# pca10040_sheet5_power_supply.net
KiCad netlist of a schematic drawn in Altium Designer
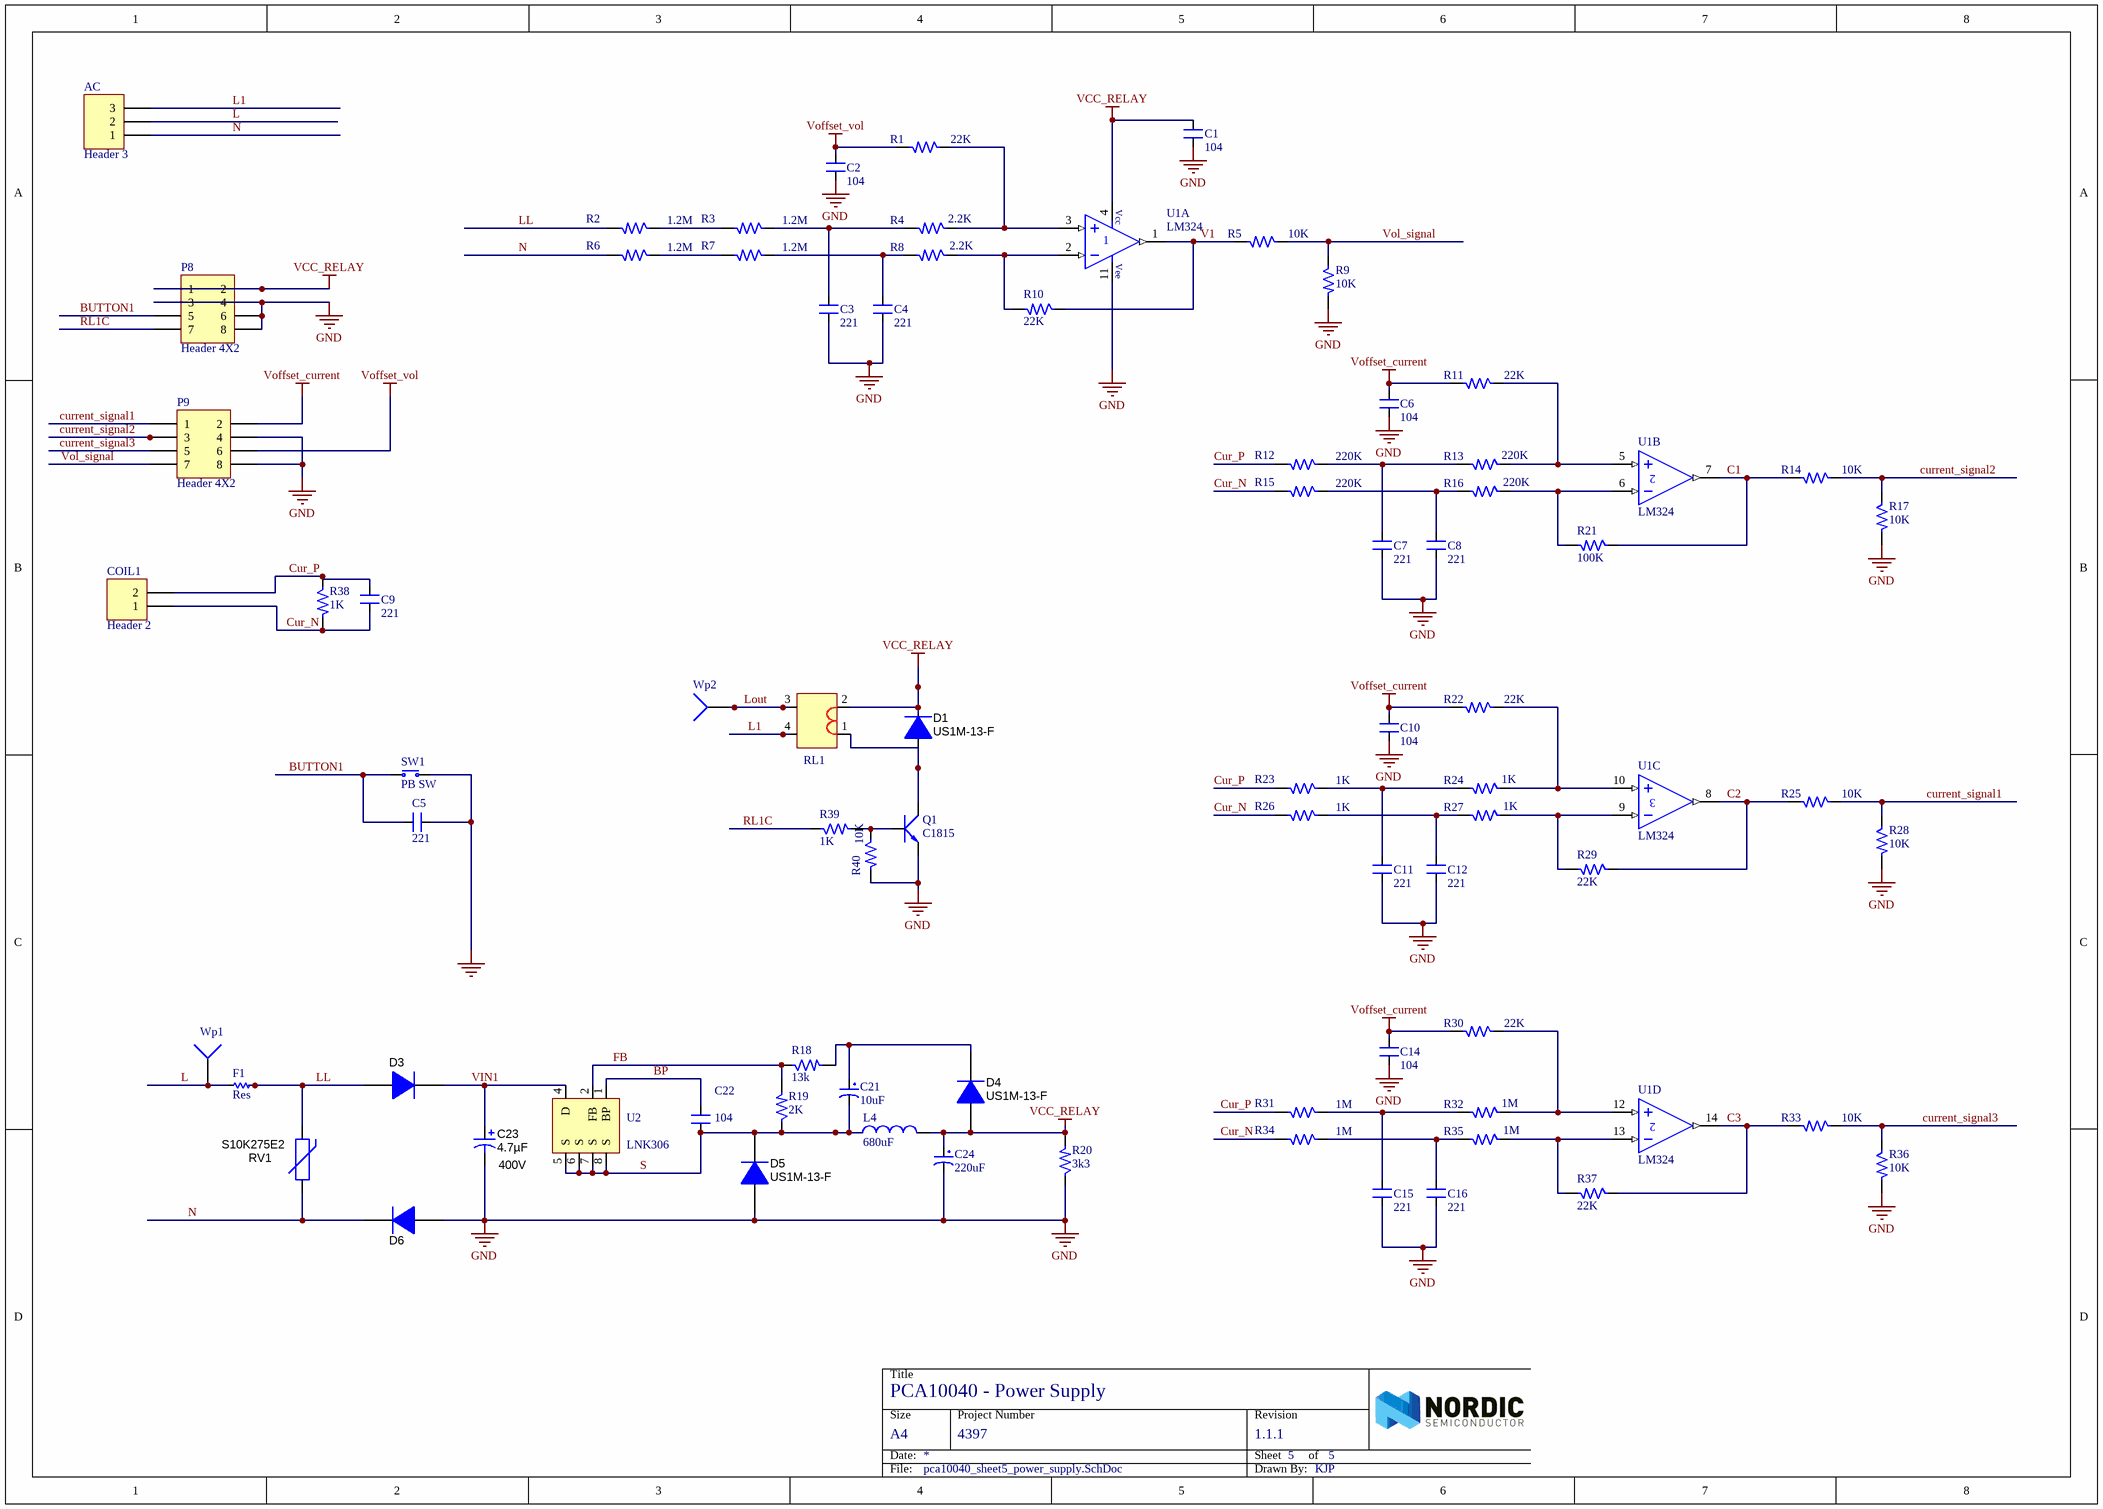
[diagram p0: pca10040_sheet5_power_supply.SchDoc]

(export (version "E")
  (design (tool "Eeschema 10.0.6"))
  (components
    (comp (ref "AC")
      (value "Header 3")
      (footprint "CHAN3DONG")
      (description "Header, 3-Pin")
      (fields (field (name "PUBLISHER") "Altium Limited"))
      (libsource (lib "Miscellaneous Connectors") (part "Header 3"))
    )
    (comp (ref "C1")
      (value "104")
      (footprint "0805_HV")
      (description "Cap SMD")
      (libsource (lib "hatcatbietbay") (part "CM"))
    )
    (comp (ref "C2")
      (value "104")
      (footprint "0805_HV")
      (description "Cap SMD")
      (libsource (lib "hatcatbietbay") (part "CM"))
    )
    (comp (ref "C3")
      (value "221")
      (footprint "0805_HV")
      (description "Cap SMD")
      (libsource (lib "hatcatbietbay") (part "CM"))
    )
    (comp (ref "C4")
      (value "221")
      (footprint "0805_HV")
      (description "Cap SMD")
      (libsource (lib "hatcatbietbay") (part "CM"))
    )
    (comp (ref "C5")
      (value "221")
      (footprint "0805_HV")
      (description "Cap SMD")
      (libsource (lib "hatcatbietbay") (part "CM"))
    )
    (comp (ref "C6")
      (value "104")
      (footprint "0805_HV")
      (description "Cap SMD")
      (libsource (lib "hatcatbietbay") (part "CM"))
    )
    (comp (ref "C7")
      (value "221")
      (footprint "0805_HV")
      (description "Cap SMD")
      (libsource (lib "hatcatbietbay") (part "CM"))
    )
    (comp (ref "C8")
      (value "221")
      (footprint "0805_HV")
      (description "Cap SMD")
      (libsource (lib "hatcatbietbay") (part "CM"))
    )
    (comp (ref "C9")
      (value "221")
      (footprint "0805_HV")
      (description "Cap SMD")
      (libsource (lib "hatcatbietbay") (part "CM"))
    )
    (comp (ref "C10")
      (value "104")
      (footprint "0805_HV")
      (description "Cap SMD")
      (libsource (lib "hatcatbietbay") (part "CM"))
    )
    (comp (ref "C11")
      (value "221")
      (footprint "0805_HV")
      (description "Cap SMD")
      (libsource (lib "hatcatbietbay") (part "CM"))
    )
    (comp (ref "C12")
      (value "221")
      (footprint "0805_HV")
      (description "Cap SMD")
      (libsource (lib "hatcatbietbay") (part "CM"))
    )
    (comp (ref "C14")
      (value "104")
      (footprint "0805_HV")
      (description "Cap SMD")
      (libsource (lib "hatcatbietbay") (part "CM"))
    )
    (comp (ref "C15")
      (value "221")
      (footprint "0805_HV")
      (description "Cap SMD")
      (libsource (lib "hatcatbietbay") (part "CM"))
    )
    (comp (ref "C16")
      (value "221")
      (footprint "0805_HV")
      (description "Cap SMD")
      (libsource (lib "hatcatbietbay") (part "CM"))
    )
    (comp (ref "C21")
      (value "10uF")
      (footprint "TU_NHOM_10uF_MH")
      (description "TU_NHOM_10uF_25V_MH")
      (libsource (lib "MH_DA_THU_VIEN_16122016") (part "TU_NHOM_10uF_25V_MH"))
    )
    (comp (ref "C22")
      (value "104")
      (footprint "0805_HV")
      (description "Cap SMD")
      (libsource (lib "hatcatbietbay") (part "CM"))
    )
    (comp (ref "C23")
      (value "400AX6R8M8x11")
      (footprint "PcbLib1:PANACAP-G-GENERIC")
      (description "CAP, AL, 6.8uF, 400V, +/-20%, TH")
      (fields
        (field (name "VALUEDISPLAYED") "4.7µF")
        (field (name "MANUFACTURER") "Rubycon")
        (field (name "VALUE2") "400V")
        (field (name "PUBLISHER") "Texas Instruments")
      )
      (libsource (lib "Capacitor_Aluminum") (part "400AX6R8M8x11"))
    )
    (comp (ref "C24")
      (value "220uF")
      (footprint "TU_NHOM_2.5_MH")
      (description "TU_NHOM_220uF_25V_MH")
      (libsource (lib "MH_DA_THU_VIEN_16122016") (part "TU_NHOM_220uF_25V_MH"))
    )
    (comp (ref "COIL1")
      (value "Header 2")
      (footprint "CURRENT_COIL")
      (description "Header, 2-Pin")
      (fields (field (name "PUBLISHER") "Altium Limited"))
      (libsource (lib "Miscellaneous Connectors") (part "Header 2"))
    )
    (comp (ref "D1")
      (value "US1M-13-F")
      (footprint "PcbLib1:SMB")
      (description "Diode, Ultrafast, 600V, 1A, SMB")
      (fields
        (field (name "PARTNUMBER") "US1M-13-F")
        (field (name "MANUFACTURER") "Diodes Inc.")
        (field (name "PUBLISHER") "Texas Instruments")
      )
      (libsource (lib "Diode") (part "MURS160-13-F"))
    )
    (comp (ref "D3")
      (value "US1M-13-F")
      (footprint "PcbLib1:SMB")
      (description "Diode, Ultrafast, 600V, 1A, SMB")
      (fields (field (name "MANUFACTURER") "Diodes Inc.") (field (name "PUBLISHER") "Texas Instruments"))
      (libsource (lib "Diode") (part "MURS160-13-F"))
    )
    (comp (ref "D4")
      (value "US1M-13-F")
      (footprint "PcbLib1:SMB")
      (description "Diode, Ultrafast, 600V, 1A, SMB")
      (fields
        (field (name "PARTNUMBER") "US1M-13-F")
        (field (name "MANUFACTURER") "Diodes Inc.")
        (field (name "PUBLISHER") "Texas Instruments")
      )
      (libsource (lib "Diode") (part "MURS160-13-F"))
    )
    (comp (ref "D5")
      (value "US1M-13-F")
      (footprint "PcbLib1:SMB")
      (description "Diode, Ultrafast, 600V, 1A, SMB")
      (fields
        (field (name "PARTNUMBER") "US1M-13-F")
        (field (name "MANUFACTURER") "Diodes Inc.")
        (field (name "PUBLISHER") "Texas Instruments")
      )
      (libsource (lib "Diode") (part "MURS160-13-F"))
    )
    (comp (ref "D6")
      (value "US1M-13-F")
      (footprint "PcbLib1:SMB")
      (description "Diode, Ultrafast, 600V, 1A, SMB")
      (fields (field (name "MANUFACTURER") "Diodes Inc.") (field (name "PUBLISHER") "Texas Instruments"))
      (libsource (lib "Diode") (part "MURS160-13-F"))
    )
    (comp (ref "F1")
      (value "Res")
      (footprint "1206")
      (description "Resistor")
      (fields
        (field (name "MANUFACTURER") "Generic Components")
        (field (name "PUBLISHER") "Altium Hobart Technology Centre")
      )
      (libsource (lib "LIBRARY") (part "Res-SMD"))
    )
    (comp (ref "L4")
      (value "680uF")
      (footprint "Inductor 4.5x5")
      (libsource (lib "MH_DA_THU_VIEN_16122016") (part "Inductor 4.5x5_MH"))
    )
    (comp (ref "P8")
      (value "Header 4X2")
      (footprint "HDR2X4")
      (description "Header, 4-Pin, Dual row")
      (fields (field (name "PUBLISHER") "Altium Limited"))
      (libsource (lib "Miscellaneous Connectors") (part "Header 4X2"))
    )
    (comp (ref "P9")
      (value "Header 4X2")
      (footprint "HDR2X4")
      (description "Header, 4-Pin, Dual row")
      (fields (field (name "PUBLISHER") "Altium Limited"))
      (libsource (lib "Miscellaneous Connectors") (part "Header 4X2"))
    )
    (comp (ref "Q1")
      (value "C1815")
      (footprint "SOT23B")
      (description "NPN 600mW, ECB")
      (libsource (lib "hatcatbietbay") (part "C1815"))
    )
    (comp (ref "R1")
      (value "22K")
      (footprint "0805_HV")
      (description "Resistor 1/4W")
      (libsource (lib "hatcatbietbay") (part "R"))
    )
    (comp (ref "R2")
      (value "1.2M")
      (footprint "1206")
      (description "Resistor 1/4W")
      (libsource (lib "hatcatbietbay") (part "R"))
    )
    (comp (ref "R3")
      (value "1.2M")
      (footprint "1206")
      (description "Resistor 1/4W")
      (libsource (lib "hatcatbietbay") (part "R"))
    )
    (comp (ref "R4")
      (value "2.2K")
      (footprint "0805_HV")
      (description "Resistor 1/4W")
      (libsource (lib "hatcatbietbay") (part "R"))
    )
    (comp (ref "R5")
      (value "10K")
      (footprint "0805_HV")
      (description "Resistor 1/4W")
      (libsource (lib "hatcatbietbay") (part "R"))
    )
    (comp (ref "R6")
      (value "1.2M")
      (footprint "1206")
      (description "Resistor 1/4W")
      (libsource (lib "hatcatbietbay") (part "R"))
    )
    (comp (ref "R7")
      (value "1.2M")
      (footprint "1206")
      (description "Resistor 1/4W")
      (libsource (lib "hatcatbietbay") (part "R"))
    )
    (comp (ref "R8")
      (value "2.2K")
      (footprint "0805_HV")
      (description "Resistor 1/4W")
      (libsource (lib "hatcatbietbay") (part "R"))
    )
    (comp (ref "R9")
      (value "10K")
      (footprint "0805_HV")
      (description "Resistor 1/4W")
      (libsource (lib "hatcatbietbay") (part "R"))
    )
    (comp (ref "R10")
      (value "22K")
      (footprint "0805_HV")
      (description "Resistor 1/4W")
      (libsource (lib "hatcatbietbay") (part "R"))
    )
    (comp (ref "R11")
      (value "22K")
      (footprint "0805_HV")
      (description "Resistor 1/4W")
      (libsource (lib "hatcatbietbay") (part "R"))
    )
    (comp (ref "R12")
      (value "220K")
      (footprint "0805_HV")
      (description "Resistor 1/4W")
      (libsource (lib "hatcatbietbay") (part "R"))
    )
    (comp (ref "R13")
      (value "220K")
      (footprint "0805_HV")
      (description "Resistor 1/4W")
      (libsource (lib "hatcatbietbay") (part "R"))
    )
    (comp (ref "R14")
      (value "10K")
      (footprint "0805_HV")
      (description "Resistor 1/4W")
      (libsource (lib "hatcatbietbay") (part "R"))
    )
    (comp (ref "R15")
      (value "220K")
      (footprint "0805_HV")
      (description "Resistor 1/4W")
      (libsource (lib "hatcatbietbay") (part "R"))
    )
    (comp (ref "R16")
      (value "220K")
      (footprint "0805_HV")
      (description "Resistor 1/4W")
      (libsource (lib "hatcatbietbay") (part "R"))
    )
    (comp (ref "R17")
      (value "10K")
      (footprint "0805_HV")
      (description "Resistor 1/4W")
      (libsource (lib "hatcatbietbay") (part "R"))
    )
    (comp (ref "R18")
      (value "13k")
      (footprint "0805_HV")
      (description "Resistor 1/4W")
      (libsource (lib "hatcatbietbay") (part "R"))
    )
    (comp (ref "R19")
      (value "2K")
      (footprint "0805_HV")
      (description "Resistor 1/4W")
      (libsource (lib "hatcatbietbay") (part "R"))
    )
    (comp (ref "R20")
      (value "3k3")
      (footprint "0805_HV")
      (description "Resistor 1/4W")
      (libsource (lib "hatcatbietbay") (part "R"))
    )
    (comp (ref "R21")
      (value "100K")
      (footprint "0805_HV")
      (description "Resistor 1/4W")
      (libsource (lib "hatcatbietbay") (part "R"))
    )
    (comp (ref "R22")
      (value "22K")
      (footprint "0805_HV")
      (description "Resistor 1/4W")
      (libsource (lib "hatcatbietbay") (part "R"))
    )
    (comp (ref "R23")
      (value "1K")
      (footprint "0805_HV")
      (description "Resistor 1/4W")
      (libsource (lib "hatcatbietbay") (part "R"))
    )
    (comp (ref "R24")
      (value "1K")
      (footprint "0805_HV")
      (description "Resistor 1/4W")
      (libsource (lib "hatcatbietbay") (part "R"))
    )
    (comp (ref "R25")
      (value "10K")
      (footprint "0805_HV")
      (description "Resistor 1/4W")
      (libsource (lib "hatcatbietbay") (part "R"))
    )
    (comp (ref "R26")
      (value "1K")
      (footprint "0805_HV")
      (description "Resistor 1/4W")
      (libsource (lib "hatcatbietbay") (part "R"))
    )
    (comp (ref "R27")
      (value "1K")
      (footprint "0805_HV")
      (description "Resistor 1/4W")
      (libsource (lib "hatcatbietbay") (part "R"))
    )
    (comp (ref "R28")
      (value "10K")
      (footprint "0805_HV")
      (description "Resistor 1/4W")
      (libsource (lib "hatcatbietbay") (part "R"))
    )
    (comp (ref "R29")
      (value "22K")
      (footprint "0805_HV")
      (description "Resistor 1/4W")
      (libsource (lib "hatcatbietbay") (part "R"))
    )
    (comp (ref "R30")
      (value "22K")
      (footprint "0805_HV")
      (description "Resistor 1/4W")
      (libsource (lib "hatcatbietbay") (part "R"))
    )
    (comp (ref "R31")
      (value "1M")
      (footprint "0805_HV")
      (description "Resistor 1/4W")
      (libsource (lib "hatcatbietbay") (part "R"))
    )
    (comp (ref "R32")
      (value "1M")
      (footprint "0805_HV")
      (description "Resistor 1/4W")
      (libsource (lib "hatcatbietbay") (part "R"))
    )
    (comp (ref "R33")
      (value "10K")
      (footprint "0805_HV")
      (description "Resistor 1/4W")
      (libsource (lib "hatcatbietbay") (part "R"))
    )
    (comp (ref "R34")
      (value "1M")
      (footprint "0805_HV")
      (description "Resistor 1/4W")
      (libsource (lib "hatcatbietbay") (part "R"))
    )
    (comp (ref "R35")
      (value "1M")
      (footprint "0805_HV")
      (description "Resistor 1/4W")
      (libsource (lib "hatcatbietbay") (part "R"))
    )
    (comp (ref "R36")
      (value "10K")
      (footprint "0805_HV")
      (description "Resistor 1/4W")
      (libsource (lib "hatcatbietbay") (part "R"))
    )
    (comp (ref "R37")
      (value "22K")
      (footprint "0805_HV")
      (description "Resistor 1/4W")
      (libsource (lib "hatcatbietbay") (part "R"))
    )
    (comp (ref "R38")
      (value "1K")
      (footprint "0805_HV")
      (description "Resistor 1/4W")
      (libsource (lib "hatcatbietbay") (part "R"))
    )
    (comp (ref "R39")
      (value "1K")
      (footprint "PcbLib1:0603")
      (description "Resistor 1/4W")
      (libsource (lib "hatcatbietbay") (part "R"))
    )
    (comp (ref "R40")
      (value "10K")
      (footprint "PcbLib1:0603")
      (description "Resistor 1/4W")
      (libsource (lib "hatcatbietbay") (part "R"))
    )
    (comp (ref "RL1")
      (value "Component_1")
      (footprint "RELAY30ASLA12VDC")
      (libsource (lib "Zettler") (part "Component_1"))
    )
    (comp (ref "RV1")
      (value "S10K275E2")
      (footprint "PcbLib1:VAR_S10K275E2")
      (description "Varistor 275V RMS 10MM Radial, TH")
      (fields
        (field (name "MANUFACTURER") "EPCOS Inc")
        (field (name "SYMBOLCREATOR") "a0412235")
        (field (name "PUBLISHER") "Texas Instruments")
      )
      (libsource (lib "Other_Passive") (part "S10K275E2"))
    )
    (comp (ref "SW1")
      (value "PB SW")
      (footprint "Switch-PB-6.2x6.3mm-SMD")
      (description "Tactile Switch, SPNO, SMD, 160gf, 6.2x6.3x2.5mm")
      (fields
        (field (name "PART NUMBER") "Switch-PB-6.2x6.3mm-SMD")
        (field (name "MANUFACTURER") "Dailywell")
        (field (name "PUBLISHER") "Nordic Semiconductor")
      )
      (libsource (lib "Nordic Discrete DB") (part "SW-PB"))
    )
    (comp (ref "U1")
      (value "LM324")
      (footprint "D014_L")
      (description "Op x 4")
      (libsource (lib "MH_DA_THU_VIEN_16122016") (part "LM324_MH"))
    )
    (comp (ref "U2") (value "LNK306") (footprint "SOP 7") (libsource (lib "LNK304") (part "Component_1")))
    (comp (ref "Wp1")
      (value "Socket")
      (footprint "PIN1")
      (fields (field (name "PUBLISHER") "Altium Limited"))
      (libsource (lib "Miscellaneous Connectors") (part "Socket"))
    )
    (comp (ref "Wp2")
      (value "Socket")
      (footprint "PIN1")
      (fields (field (name "PUBLISHER") "Altium Limited"))
      (libsource (lib "Miscellaneous Connectors") (part "Socket"))
    )
  )
  (nets
    (net (code "1") (name "/BP") (class "Default")
      (node (ref "C22") (pin "2") (pinfunction "2_2") (pintype "passive"))
      (node (ref "U2") (pin "1") (pinfunction "BP_1") (pintype "passive"))
    )
    (net (code "2") (name "/BUTTON1") (class "Default")
      (node (ref "C5") (pin "2") (pinfunction "2_2") (pintype "passive"))
      (node (ref "P8") (pin "5") (pinfunction "5_5") (pintype "passive"))
      (node (ref "SW1") (pin "2") (pinfunction "COM_2") (pintype "passive"))
    )
    (net (code "3") (name "/C1") (class "Default")
      (node (ref "R14") (pin "2") (pinfunction "2_2") (pintype "passive"))
      (node (ref "R21") (pin "1") (pinfunction "1_1") (pintype "passive"))
      (node (ref "U1") (pin "7") (pinfunction "OUT_7") (pintype "output"))
    )
    (net (code "4") (name "/C2") (class "Default")
      (node (ref "R25") (pin "2") (pinfunction "2_2") (pintype "passive"))
      (node (ref "R29") (pin "1") (pinfunction "1_1") (pintype "passive"))
      (node (ref "U1") (pin "8") (pinfunction "OUT_8") (pintype "output"))
    )
    (net (code "5") (name "/C3") (class "Default")
      (node (ref "R33") (pin "2") (pinfunction "2_2") (pintype "passive"))
      (node (ref "R37") (pin "1") (pinfunction "1_1") (pintype "passive"))
      (node (ref "U1") (pin "14") (pinfunction "OUT_14") (pintype "output"))
    )
    (net (code "6") (name "/Cur_N") (class "Default")
      (node (ref "C9") (pin "1") (pinfunction "1_1") (pintype "passive"))
      (node (ref "COIL1") (pin "1") (pinfunction "1_1") (pintype "passive"))
      (node (ref "R15") (pin "2") (pinfunction "2_2") (pintype "passive"))
      (node (ref "R26") (pin "2") (pinfunction "2_2") (pintype "passive"))
      (node (ref "R34") (pin "2") (pinfunction "2_2") (pintype "passive"))
      (node (ref "R38") (pin "2") (pinfunction "2_2") (pintype "passive"))
    )
    (net (code "7") (name "/Cur_P") (class "Default")
      (node (ref "C9") (pin "2") (pinfunction "2_2") (pintype "passive"))
      (node (ref "COIL1") (pin "2") (pinfunction "2_2") (pintype "passive"))
      (node (ref "R12") (pin "2") (pinfunction "2_2") (pintype "passive"))
      (node (ref "R23") (pin "2") (pinfunction "2_2") (pintype "passive"))
      (node (ref "R31") (pin "2") (pinfunction "2_2") (pintype "passive"))
      (node (ref "R38") (pin "1") (pinfunction "1_1") (pintype "passive"))
    )
    (net (code "8") (name "/FB") (class "Default")
      (node (ref "R18") (pin "1") (pinfunction "1_1") (pintype "passive"))
      (node (ref "R19") (pin "2") (pinfunction "2_2") (pintype "passive"))
      (node (ref "U2") (pin "2") (pinfunction "FB_2") (pintype "passive"))
    )
    (net (code "9") (name "/L") (class "Default")
      (node (ref "AC") (pin "2") (pinfunction "2_2") (pintype "passive"))
      (node (ref "F1") (pin "2") (pinfunction "2_2") (pintype "passive"))
      (node (ref "Wp1") (pin "1") (pinfunction "1_1") (pintype "passive"))
    )
    (net (code "10") (name "/L1") (class "Default")
      (node (ref "AC") (pin "3") (pinfunction "3_3") (pintype "passive"))
      (node (ref "RL1") (pin "4") (pintype "passive"))
    )
    (net (code "11") (name "/LL") (class "Default")
      (node (ref "D3") (pin "2") (pinfunction "A_2") (pintype "passive"))
      (node (ref "F1") (pin "1") (pinfunction "1_1") (pintype "passive"))
      (node (ref "R2") (pin "2") (pinfunction "2_2") (pintype "passive"))
      (node (ref "RV1") (pin "2") (pinfunction "2_2") (pintype "passive"))
    )
    (net (code "12") (name "/Lout") (class "Default")
      (node (ref "RL1") (pin "3") (pintype "passive"))
      (node (ref "Wp2") (pin "1") (pinfunction "1_1") (pintype "passive"))
    )
    (net (code "13") (name "/N") (class "Default")
      (node (ref "AC") (pin "1") (pinfunction "1_1") (pintype "passive"))
      (node (ref "D6") (pin "1") (pinfunction "K_1") (pintype "passive"))
      (node (ref "R6") (pin "2") (pinfunction "2_2") (pintype "passive"))
      (node (ref "RV1") (pin "1") (pinfunction "1_1") (pintype "passive"))
    )
    (net (code "14") (name "/RL1C") (class "Default")
      (node (ref "P8") (pin "7") (pinfunction "7_7") (pintype "passive"))
      (node (ref "R39") (pin "1") (pinfunction "1_1") (pintype "passive"))
    )
    (net (code "15") (name "/S") (class "Default")
      (node (ref "C21") (pin "2") (pinfunction "2_2") (pintype "passive"))
      (node (ref "C22") (pin "1") (pinfunction "1_1") (pintype "passive"))
      (node (ref "D5") (pin "1") (pinfunction "K_1") (pintype "passive"))
      (node (ref "L4") (pin "1") (pinfunction "1_1") (pintype "passive"))
      (node (ref "R19") (pin "1") (pinfunction "1_1") (pintype "passive"))
      (node (ref "U2") (pin "5") (pinfunction "S_5") (pintype "passive"))
      (node (ref "U2") (pin "6") (pinfunction "S_6") (pintype "passive"))
      (node (ref "U2") (pin "7") (pinfunction "S_7") (pintype "passive"))
      (node (ref "U2") (pin "8") (pinfunction "S_8") (pintype "passive"))
    )
    (net (code "16") (name "/V1") (class "Default")
      (node (ref "R10") (pin "1") (pinfunction "1_1") (pintype "passive"))
      (node (ref "R5") (pin "2") (pinfunction "2_2") (pintype "passive"))
      (node (ref "U1") (pin "1") (pinfunction "OUT_1") (pintype "output"))
    )
    (net (code "17") (name "/VIN1") (class "Default")
      (node (ref "C23") (pin "1") (pinfunction "+_1") (pintype "passive"))
      (node (ref "D3") (pin "1") (pinfunction "K_1") (pintype "passive"))
      (node (ref "U2") (pin "4") (pinfunction "D_4") (pintype "passive"))
    )
    (net (code "18") (name "/Vol_signal") (class "Default")
      (node (ref "P9") (pin "7") (pinfunction "7_7") (pintype "passive"))
      (node (ref "R5") (pin "1") (pinfunction "1_1") (pintype "passive"))
      (node (ref "R9") (pin "1") (pinfunction "1_1") (pintype "passive"))
    )
    (net (code "19") (name "/current_signal1") (class "Default")
      (node (ref "P9") (pin "1") (pinfunction "1_1") (pintype "passive"))
      (node (ref "R25") (pin "1") (pinfunction "1_1") (pintype "passive"))
      (node (ref "R28") (pin "1") (pinfunction "1_1") (pintype "passive"))
    )
    (net (code "20") (name "/current_signal2") (class "Default")
      (node (ref "P9") (pin "3") (pinfunction "3_3") (pintype "passive"))
      (node (ref "R14") (pin "1") (pinfunction "1_1") (pintype "passive"))
      (node (ref "R17") (pin "1") (pinfunction "1_1") (pintype "passive"))
    )
    (net (code "21") (name "/current_signal3") (class "Default")
      (node (ref "P9") (pin "5") (pinfunction "5_5") (pintype "passive"))
      (node (ref "R33") (pin "1") (pinfunction "1_1") (pintype "passive"))
      (node (ref "R36") (pin "1") (pinfunction "1_1") (pintype "passive"))
    )
    (net (code "22") (name "GND") (class "Default")
      (node (ref "C1") (pin "1") (pinfunction "1_1") (pintype "passive"))
      (node (ref "C10") (pin "1") (pinfunction "1_1") (pintype "passive"))
      (node (ref "C11") (pin "1") (pinfunction "1_1") (pintype "passive"))
      (node (ref "C12") (pin "1") (pinfunction "1_1") (pintype "passive"))
      (node (ref "C14") (pin "1") (pinfunction "1_1") (pintype "passive"))
      (node (ref "C15") (pin "1") (pinfunction "1_1") (pintype "passive"))
      (node (ref "C16") (pin "1") (pinfunction "1_1") (pintype "passive"))
      (node (ref "C2") (pin "1") (pinfunction "1_1") (pintype "passive"))
      (node (ref "C23") (pin "2") (pinfunction "-_2") (pintype "passive"))
      (node (ref "C24") (pin "2") (pinfunction "2_2") (pintype "passive"))
      (node (ref "C3") (pin "1") (pinfunction "1_1") (pintype "passive"))
      (node (ref "C4") (pin "1") (pinfunction "1_1") (pintype "passive"))
      (node (ref "C5") (pin "1") (pinfunction "1_1") (pintype "passive"))
      (node (ref "C6") (pin "1") (pinfunction "1_1") (pintype "passive"))
      (node (ref "C7") (pin "1") (pinfunction "1_1") (pintype "passive"))
      (node (ref "C8") (pin "1") (pinfunction "1_1") (pintype "passive"))
      (node (ref "D5") (pin "2") (pinfunction "A_2") (pintype "passive"))
      (node (ref "D6") (pin "2") (pinfunction "A_2") (pintype "passive"))
      (node (ref "P8") (pin "3") (pinfunction "3_3") (pintype "passive"))
      (node (ref "P8") (pin "4") (pinfunction "4_4") (pintype "passive"))
      (node (ref "P8") (pin "6") (pinfunction "6_6") (pintype "passive"))
      (node (ref "P8") (pin "8") (pinfunction "8_8") (pintype "passive"))
      (node (ref "P9") (pin "4") (pinfunction "4_4") (pintype "passive"))
      (node (ref "P9") (pin "8") (pinfunction "8_8") (pintype "passive"))
      (node (ref "Q1") (pin "3") (pinfunction "E_3") (pintype "passive"))
      (node (ref "R17") (pin "2") (pinfunction "2_2") (pintype "passive"))
      (node (ref "R20") (pin "1") (pinfunction "1_1") (pintype "passive"))
      (node (ref "R28") (pin "2") (pinfunction "2_2") (pintype "passive"))
      (node (ref "R36") (pin "2") (pinfunction "2_2") (pintype "passive"))
      (node (ref "R40") (pin "2") (pinfunction "2_2") (pintype "passive"))
      (node (ref "R9") (pin "2") (pinfunction "2_2") (pintype "passive"))
      (node (ref "SW1") (pin "1") (pinfunction "N.O_1") (pintype "passive"))
      (node (ref "U1") (pin "11") (pinfunction "V-_11") (pintype "power_in"))
    )
    (net (code "23") (name "Net-(C3-Pad2)") (class "Default")
      (node (ref "C3") (pin "2") (pinfunction "2_2") (pintype "passive"))
      (node (ref "R3") (pin "1") (pinfunction "1_1") (pintype "passive"))
      (node (ref "R4") (pin "2") (pinfunction "2_2") (pintype "passive"))
    )
    (net (code "24") (name "Net-(C4-Pad2)") (class "Default")
      (node (ref "C4") (pin "2") (pinfunction "2_2") (pintype "passive"))
      (node (ref "R7") (pin "1") (pinfunction "1_1") (pintype "passive"))
      (node (ref "R8") (pin "2") (pinfunction "2_2") (pintype "passive"))
    )
    (net (code "25") (name "Net-(C7-Pad2)") (class "Default")
      (node (ref "C7") (pin "2") (pinfunction "2_2") (pintype "passive"))
      (node (ref "R12") (pin "1") (pinfunction "1_1") (pintype "passive"))
      (node (ref "R13") (pin "2") (pinfunction "2_2") (pintype "passive"))
    )
    (net (code "26") (name "Net-(C8-Pad2)") (class "Default")
      (node (ref "C8") (pin "2") (pinfunction "2_2") (pintype "passive"))
      (node (ref "R15") (pin "1") (pinfunction "1_1") (pintype "passive"))
      (node (ref "R16") (pin "2") (pinfunction "2_2") (pintype "passive"))
    )
    (net (code "27") (name "Net-(C11-Pad2)") (class "Default")
      (node (ref "C11") (pin "2") (pinfunction "2_2") (pintype "passive"))
      (node (ref "R23") (pin "1") (pinfunction "1_1") (pintype "passive"))
      (node (ref "R24") (pin "2") (pinfunction "2_2") (pintype "passive"))
    )
    (net (code "28") (name "Net-(C12-Pad2)") (class "Default")
      (node (ref "C12") (pin "2") (pinfunction "2_2") (pintype "passive"))
      (node (ref "R26") (pin "1") (pinfunction "1_1") (pintype "passive"))
      (node (ref "R27") (pin "2") (pinfunction "2_2") (pintype "passive"))
    )
    (net (code "29") (name "Net-(C15-Pad2)") (class "Default")
      (node (ref "C15") (pin "2") (pinfunction "2_2") (pintype "passive"))
      (node (ref "R31") (pin "1") (pinfunction "1_1") (pintype "passive"))
      (node (ref "R32") (pin "2") (pinfunction "2_2") (pintype "passive"))
    )
    (net (code "30") (name "Net-(C16-Pad2)") (class "Default")
      (node (ref "C16") (pin "2") (pinfunction "2_2") (pintype "passive"))
      (node (ref "R34") (pin "1") (pinfunction "1_1") (pintype "passive"))
      (node (ref "R35") (pin "2") (pinfunction "2_2") (pintype "passive"))
    )
    (net (code "31") (name "Net-(D1-A)") (class "Default")
      (node (ref "D1") (pin "2") (pinfunction "A_2") (pintype "passive"))
      (node (ref "Q1") (pin "2") (pinfunction "C_2") (pintype "passive"))
      (node (ref "RL1") (pin "1") (pintype "passive"))
    )
    (net (code "32") (name "Net-(D4-K)") (class "Default")
      (node (ref "C21") (pin "1") (pinfunction "1_1") (pintype "passive"))
      (node (ref "D4") (pin "1") (pinfunction "K_1") (pintype "passive"))
      (node (ref "R18") (pin "2") (pinfunction "2_2") (pintype "passive"))
    )
    (net (code "33") (name "Net-(Q1-B)") (class "Default")
      (node (ref "Q1") (pin "1") (pinfunction "B_1") (pintype "passive"))
      (node (ref "R39") (pin "2") (pinfunction "2_2") (pintype "passive"))
      (node (ref "R40") (pin "1") (pinfunction "1_1") (pintype "passive"))
    )
    (net (code "34") (name "Net-(R2-Pad1)") (class "Default")
      (node (ref "R2") (pin "1") (pinfunction "1_1") (pintype "passive"))
      (node (ref "R3") (pin "2") (pinfunction "2_2") (pintype "passive"))
    )
    (net (code "35") (name "Net-(R6-Pad1)") (class "Default")
      (node (ref "R6") (pin "1") (pinfunction "1_1") (pintype "passive"))
      (node (ref "R7") (pin "2") (pinfunction "2_2") (pintype "passive"))
    )
    (net (code "36") (name "Net-(U1A-IN+)") (class "Default")
      (node (ref "R1") (pin "1") (pinfunction "1_1") (pintype "passive"))
      (node (ref "R4") (pin "1") (pinfunction "1_1") (pintype "passive"))
      (node (ref "U1") (pin "3") (pinfunction "IN+_3") (pintype "input"))
    )
    (net (code "37") (name "Net-(U1A-IN-)") (class "Default")
      (node (ref "R10") (pin "2") (pinfunction "2_2") (pintype "passive"))
      (node (ref "R8") (pin "1") (pinfunction "1_1") (pintype "passive"))
      (node (ref "U1") (pin "2") (pinfunction "IN-_2") (pintype "input"))
    )
    (net (code "38") (name "Net-(U1B-IN+)") (class "Default")
      (node (ref "R11") (pin "1") (pinfunction "1_1") (pintype "passive"))
      (node (ref "R13") (pin "1") (pinfunction "1_1") (pintype "passive"))
      (node (ref "U1") (pin "5") (pinfunction "IN+_5") (pintype "input"))
    )
    (net (code "39") (name "Net-(U1B-IN-)") (class "Default")
      (node (ref "R16") (pin "1") (pinfunction "1_1") (pintype "passive"))
      (node (ref "R21") (pin "2") (pinfunction "2_2") (pintype "passive"))
      (node (ref "U1") (pin "6") (pinfunction "IN-_6") (pintype "input"))
    )
    (net (code "40") (name "Net-(U1C-IN+)") (class "Default")
      (node (ref "R22") (pin "1") (pinfunction "1_1") (pintype "passive"))
      (node (ref "R24") (pin "1") (pinfunction "1_1") (pintype "passive"))
      (node (ref "U1") (pin "10") (pinfunction "IN+_10") (pintype "input"))
    )
    (net (code "41") (name "Net-(U1C-IN-)") (class "Default")
      (node (ref "R27") (pin "1") (pinfunction "1_1") (pintype "passive"))
      (node (ref "R29") (pin "2") (pinfunction "2_2") (pintype "passive"))
      (node (ref "U1") (pin "9") (pinfunction "IN-_9") (pintype "input"))
    )
    (net (code "42") (name "Net-(U1D-IN+)") (class "Default")
      (node (ref "R30") (pin "1") (pinfunction "1_1") (pintype "passive"))
      (node (ref "R32") (pin "1") (pinfunction "1_1") (pintype "passive"))
      (node (ref "U1") (pin "12") (pinfunction "IN+_12") (pintype "input"))
    )
    (net (code "43") (name "Net-(U1D-IN-)") (class "Default")
      (node (ref "R35") (pin "1") (pinfunction "1_1") (pintype "passive"))
      (node (ref "R37") (pin "2") (pinfunction "2_2") (pintype "passive"))
      (node (ref "U1") (pin "13") (pinfunction "IN-_13") (pintype "input"))
    )
    (net (code "44") (name "VCC_RELAY") (class "Default")
      (node (ref "C1") (pin "2") (pinfunction "2_2") (pintype "passive"))
      (node (ref "C24") (pin "1") (pinfunction "1_1") (pintype "passive"))
      (node (ref "D1") (pin "1") (pinfunction "K_1") (pintype "passive"))
      (node (ref "D4") (pin "2") (pinfunction "A_2") (pintype "passive"))
      (node (ref "L4") (pin "2") (pinfunction "2_2") (pintype "passive"))
      (node (ref "P8") (pin "1") (pinfunction "1_1") (pintype "passive"))
      (node (ref "P8") (pin "2") (pinfunction "2_2") (pintype "passive"))
      (node (ref "R20") (pin "2") (pinfunction "2_2") (pintype "passive"))
      (node (ref "RL1") (pin "2") (pintype "passive"))
      (node (ref "U1") (pin "4") (pinfunction "V+_4") (pintype "power_in"))
    )
    (net (code "45") (name "Voffset_current") (class "Default")
      (node (ref "C10") (pin "2") (pinfunction "2_2") (pintype "passive"))
      (node (ref "C14") (pin "2") (pinfunction "2_2") (pintype "passive"))
      (node (ref "C6") (pin "2") (pinfunction "2_2") (pintype "passive"))
      (node (ref "P9") (pin "2") (pinfunction "2_2") (pintype "passive"))
      (node (ref "R11") (pin "2") (pinfunction "2_2") (pintype "passive"))
      (node (ref "R22") (pin "2") (pinfunction "2_2") (pintype "passive"))
      (node (ref "R30") (pin "2") (pinfunction "2_2") (pintype "passive"))
    )
    (net (code "46") (name "Voffset_vol") (class "Default")
      (node (ref "C2") (pin "2") (pinfunction "2_2") (pintype "passive"))
      (node (ref "P9") (pin "6") (pinfunction "6_6") (pintype "passive"))
      (node (ref "R1") (pin "2") (pinfunction "2_2") (pintype "passive"))
    )
  )
)
